# dsPIC_Click_Analog_v1_5.net
KiCad netlist of a schematic drawn in Altium Designer
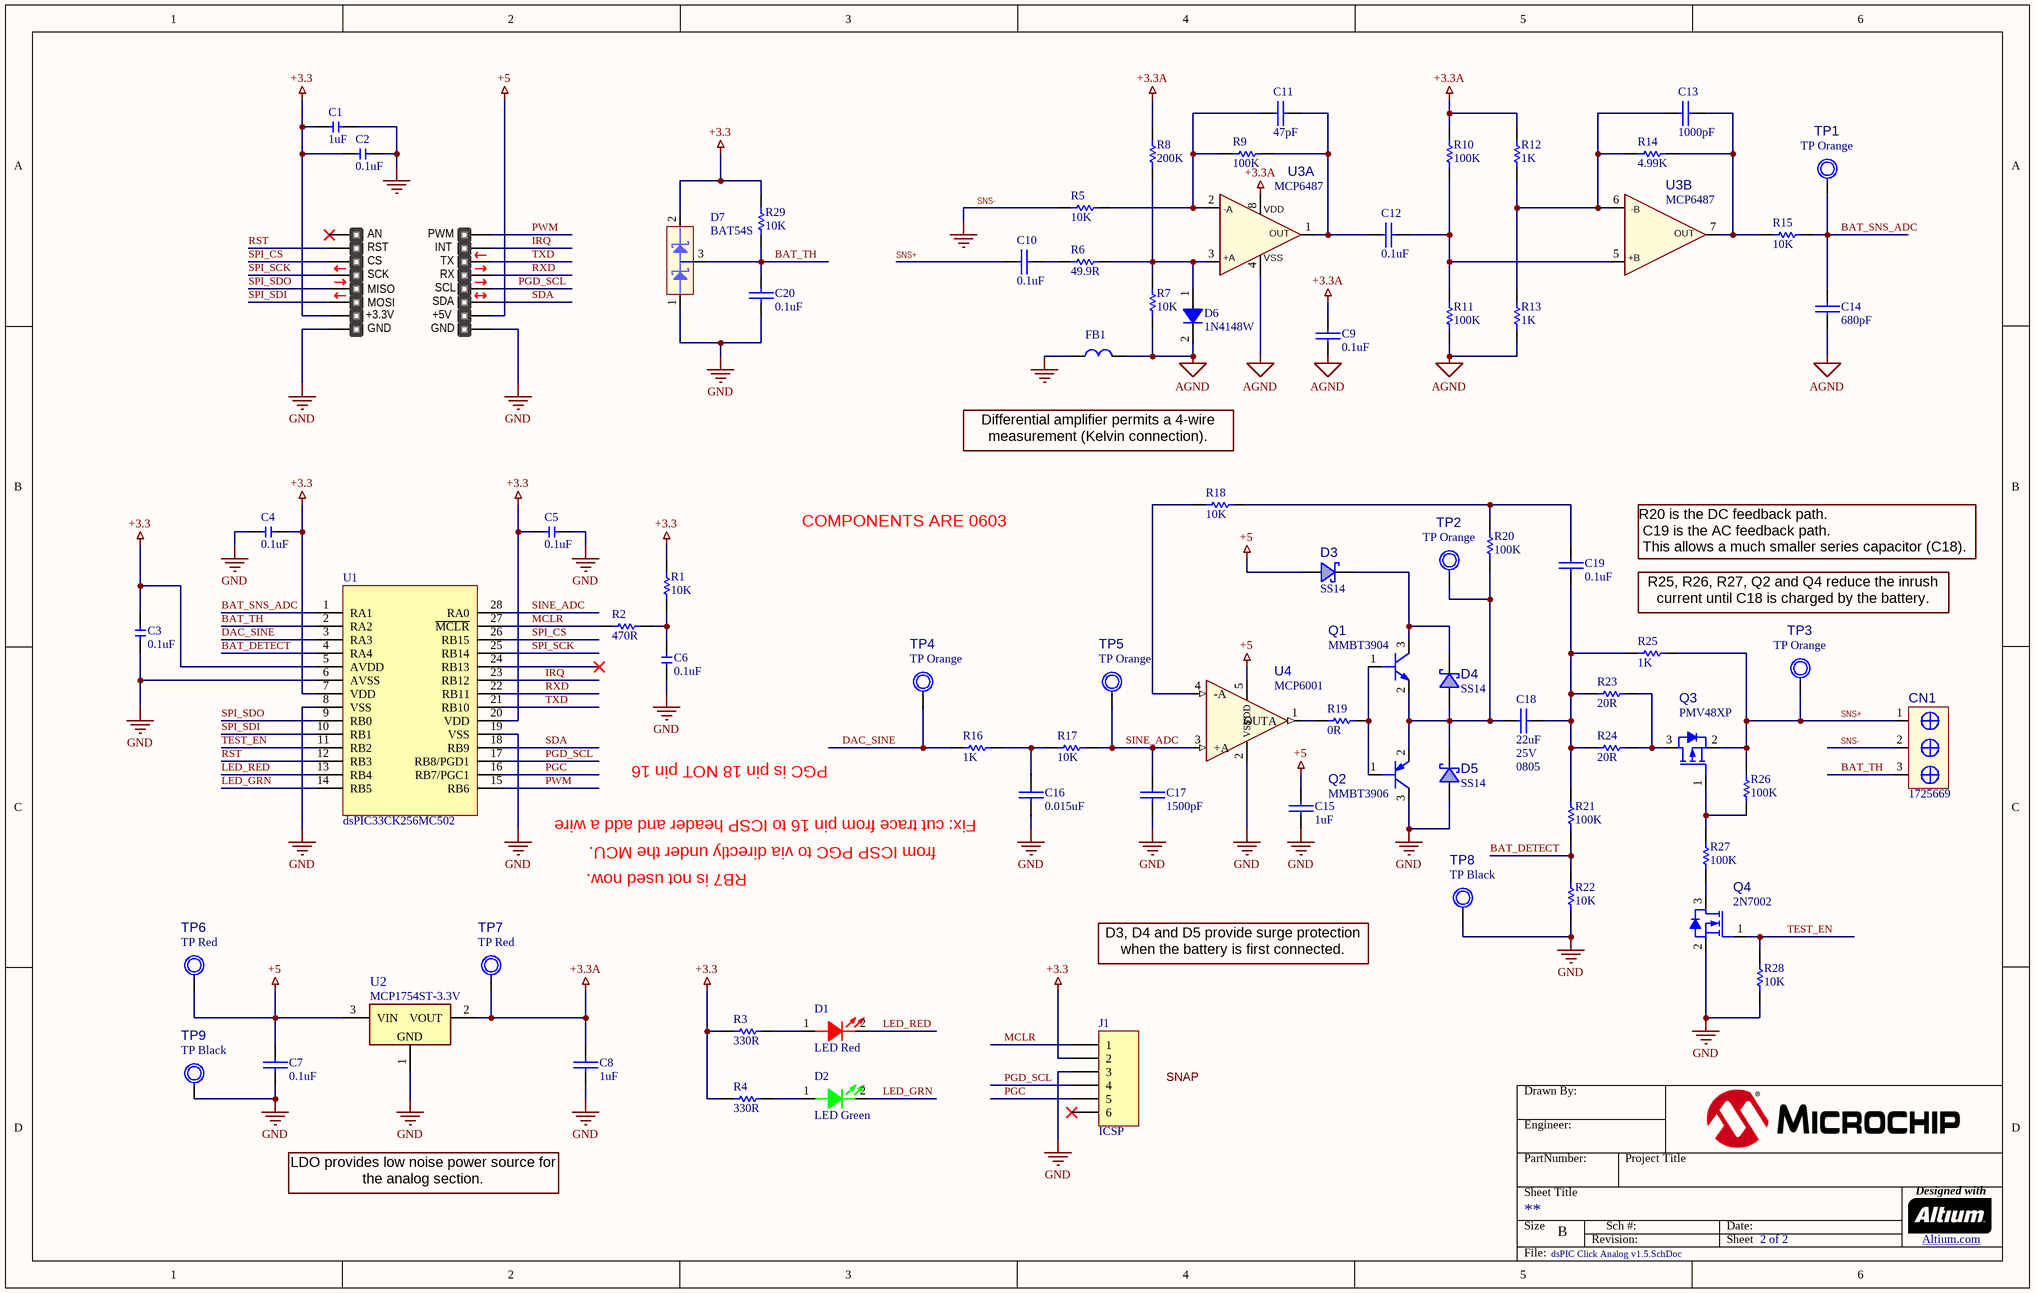
[diagram p0: dsPIC Click Analog v1.5.SchDoc]

(export (version "E")
  (design (tool "Eeschema 10.0.6"))
  (components
    (comp (ref "C1")
      (value "1uF")
      (footprint "0603C")
      (description "Capacitor")
      (libsource (lib "dsPIC Click_2") (part "Capacitor NP"))
    )
    (comp (ref "C2")
      (value "0.1uF")
      (footprint "0603C")
      (description "Capacitor")
      (libsource (lib "dsPIC Click_2") (part "Capacitor NP"))
    )
    (comp (ref "C3")
      (value "0.1uF")
      (footprint "0603C")
      (description "Capacitor")
      (libsource (lib "dsPIC Click_2") (part "Capacitor NP"))
    )
    (comp (ref "C4")
      (value "0.1uF")
      (footprint "0603C")
      (description "Capacitor")
      (libsource (lib "dsPIC Click_2") (part "Capacitor NP"))
    )
    (comp (ref "C5")
      (value "0.1uF")
      (footprint "0603C")
      (description "Capacitor")
      (libsource (lib "dsPIC Click_2") (part "Capacitor NP"))
    )
    (comp (ref "C6")
      (value "0.1uF")
      (footprint "0603C")
      (description "Capacitor")
      (libsource (lib "dsPIC Click_2") (part "Capacitor NP"))
    )
    (comp (ref "C7")
      (value "0.1uF")
      (footprint "0603C")
      (description "Capacitor")
      (libsource (lib "dsPIC Click_2") (part "CAP"))
    )
    (comp (ref "C8")
      (value "1uF")
      (footprint "0603C")
      (description "Capacitor")
      (libsource (lib "dsPIC Click_2") (part "CAP"))
    )
    (comp (ref "C9")
      (value "0.1uF")
      (footprint "0603C")
      (description "Capacitor")
      (libsource (lib "dsPIC Click_2") (part "CAP"))
    )
    (comp (ref "C10")
      (value "0.1uF")
      (footprint "0603C")
      (description "Capacitor")
      (libsource (lib "dsPIC Click_2") (part "CAP"))
    )
    (comp (ref "C11")
      (value "47pF")
      (footprint "0603C")
      (description "Capacitor")
      (libsource (lib "dsPIC Click_2") (part "CAP"))
    )
    (comp (ref "C12")
      (value "0.1uF")
      (footprint "0603C")
      (description "Capacitor")
      (libsource (lib "dsPIC Click_2") (part "CAP"))
    )
    (comp (ref "C13")
      (value "1000pF")
      (footprint "0603C")
      (description "Capacitor")
      (libsource (lib "dsPIC Click_2") (part "CAP"))
    )
    (comp (ref "C14")
      (value "680pF")
      (footprint "0603C")
      (description "Capacitor")
      (libsource (lib "dsPIC Click_2") (part "CAP"))
    )
    (comp (ref "C15")
      (value "1uF")
      (footprint "0603C")
      (description "Capacitor")
      (libsource (lib "dsPIC Click_2") (part "CAP"))
    )
    (comp (ref "C16")
      (value "0.015uF")
      (footprint "0603C")
      (description "Capacitor")
      (libsource (lib "dsPIC Click_2") (part "CAP"))
    )
    (comp (ref "C17")
      (value "1500pF")
      (footprint "0603C")
      (description "Capacitor")
      (libsource (lib "dsPIC Click_2") (part "CAP"))
    )
    (comp (ref "C18")
      (value "22uF")
      (footprint "0805C")
      (description "Capacitor")
      (fields (field (name "ALTIUM_UNNAMED_1") "25V") (field (name "ALTIUM_UNNAMED_2") "0805"))
      (libsource (lib "dsPIC Click_2") (part "CAP"))
    )
    (comp (ref "C19")
      (value "0.1uF")
      (footprint "0603C")
      (description "Capacitor")
      (libsource (lib "dsPIC Click_2") (part "CAP"))
    )
    (comp (ref "C20")
      (value "0.1uF")
      (footprint "0603C")
      (description "Capacitor")
      (libsource (lib "dsPIC Click_2") (part "CAP"))
    )
    (comp (ref "CN1")
      (value "1725669")
      (footprint "1725669")
      (description "Terminal Block, 3-Position")
      (fields (field (name "VOLTAGE") "63V") (field (name "OWNER") "Sorin Stanoaia"))
      (libsource (lib "dsPIC Click_2") (part "1725669"))
    )
    (comp (ref "D1")
      (value "LED Red")
      (footprint "LTST-C171")
      (description "Red LED")
      (fields (field (name "POWER") "50mW") (field (name "OWNER") "Stephen Humberd"))
      (libsource (lib "dsPIC Click_2") (part "LED_RED"))
    )
    (comp (ref "D2")
      (value "LED Green")
      (footprint "LTST-C171")
      (description "Green LED")
      (fields (field (name "POWER") "50mW") (field (name "OWNER") "Stephen Humberd"))
      (libsource (lib "dsPIC Click_2") (part "LED_GRN"))
    )
    (comp (ref "D3")
      (value "SS14")
      (footprint "SMA-FL")
      (description "Diode, Schottky")
      (fields (field (name "POWER") "1.1W"))
      (libsource (lib "dsPIC Click_2") (part "SS14"))
    )
    (comp (ref "D4")
      (value "SS14")
      (footprint "SMA-FL")
      (description "Diode, Schottky")
      (fields (field (name "POWER") "1.1W"))
      (libsource (lib "dsPIC Click_2") (part "SS14"))
    )
    (comp (ref "D5")
      (value "SS14")
      (footprint "SMA-FL")
      (description "Diode, Schottky")
      (fields (field (name "POWER") "1.1W"))
      (libsource (lib "dsPIC Click_2") (part "SS14"))
    )
    (comp (ref "D6")
      (value "1N4148W")
      (footprint "SOD-123")
      (description "1N4148W, SOD-123")
      (libsource (lib "dsPIC Click_2") (part "1N4148W"))
    )
    (comp (ref "D7")
      (value "BAT54S")
      (footprint "SOT-23")
      (description "Schottky Diode, Dual, Common Cathode")
      (fields (field (name "PUBLISHER") "Altium Limited"))
      (libsource (lib "dsPIC Click_2") (part "BAT54S"))
    )
    (comp (ref "FB1")
      (value "FB")
      (footprint "0603FB")
      (description "Ferrite Bead")
      (libsource (lib "dsPIC Click_2") (part "FB"))
    )
    (comp (ref "J1")
      (value "ICSP")
      (footprint "HDR1X6")
      (description "Header, 6-Pin")
      (fields (field (name "PUBLISHER") "Altium Limited"))
      (libsource (lib "dsPIC Click_2") (part "Header 6"))
    )
    (comp (ref "MIKROBUS CONNECTOR")
      (value "MIKROBUS DEVICE CONN.")
      (footprint "MIKRO_BUS_dsPIC_T")
      (description "mikroBUS Target Header")
      (libsource (lib "dsPIC Click_2") (part "MIKROBUS DEVICE CONN."))
    )
    (comp (ref "Q1")
      (value "MMBT3904")
      (footprint "SOT-23")
      (description "Transistor, NPN")
      (fields (field (name "POWER") "310mW") (field (name "VOLTAGE") "40V"))
      (libsource (lib "dsPIC Click_2") (part "MMBT3904"))
    )
    (comp (ref "Q2")
      (value "MMBT3906")
      (footprint "SOT-23")
      (description "Transistor, PNP")
      (fields (field (name "POWER") "300mW") (field (name "VOLTAGE") "-40V"))
      (libsource (lib "dsPIC Click_2") (part "MMBT3906"))
    )
    (comp (ref "Q3")
      (value "PMV48XP")
      (footprint "SOT-23")
      (description "MOSFET, P-Channel")
      (fields (field (name "POWER") "510mW") (field (name "OWNER") "Gabor Bihari"))
      (libsource (lib "dsPIC Click_2") (part "PMV48XP"))
    )
    (comp (ref "Q4")
      (value "2N7002")
      (footprint "SOT-23")
      (description "MOSFET")
      (fields (field (name "POWER") "370mW") (field (name "OWNER") "Adrian M (M91404)"))
      (libsource (lib "dsPIC Click_2") (part "2N7002"))
    )
    (comp (ref "R1")
      (value "10K")
      (footprint "0603R")
      (description "Resistor")
      (fields (field (name "PUBLISHER") "Altium Limited"))
      (libsource (lib "dsPIC Click_2") (part "Res1"))
    )
    (comp (ref "R2")
      (value "470R")
      (footprint "0603R")
      (description "Resistor")
      (fields (field (name "PUBLISHER") "Altium Limited"))
      (libsource (lib "dsPIC Click_2") (part "Res1"))
    )
    (comp (ref "R3")
      (value "330R")
      (footprint "0603R")
      (description "Resistor")
      (fields (field (name "PUBLISHER") "Altium Limited"))
      (libsource (lib "dsPIC Click_2") (part "Res1"))
    )
    (comp (ref "R4")
      (value "330R")
      (footprint "0603R")
      (description "Resistor")
      (fields (field (name "PUBLISHER") "Altium Limited"))
      (libsource (lib "dsPIC Click_2") (part "Res1"))
    )
    (comp (ref "R5")
      (value "10K")
      (footprint "0603R")
      (description "Resistor")
      (fields (field (name "PUBLISHER") "Altium Limited"))
      (libsource (lib "dsPIC Click_2") (part "Res1"))
    )
    (comp (ref "R6")
      (value "49.9R")
      (footprint "0603R")
      (description "Resistor")
      (fields (field (name "PUBLISHER") "Altium Limited"))
      (libsource (lib "dsPIC Click_2") (part "Res1"))
    )
    (comp (ref "R7")
      (value "10K")
      (footprint "0603R")
      (description "Resistor")
      (fields (field (name "PUBLISHER") "Altium Limited"))
      (libsource (lib "dsPIC Click_2") (part "Res1"))
    )
    (comp (ref "R8")
      (value "200K")
      (footprint "0603R")
      (description "Resistor")
      (fields (field (name "PUBLISHER") "Altium Limited"))
      (libsource (lib "dsPIC Click_2") (part "Res1"))
    )
    (comp (ref "R9")
      (value "100K")
      (footprint "0603R")
      (description "Resistor")
      (fields (field (name "PUBLISHER") "Altium Limited"))
      (libsource (lib "dsPIC Click_2") (part "Res1"))
    )
    (comp (ref "R10")
      (value "100K")
      (footprint "0603R")
      (description "Resistor")
      (fields (field (name "PUBLISHER") "Altium Limited"))
      (libsource (lib "dsPIC Click_2") (part "Res1"))
    )
    (comp (ref "R11")
      (value "100K")
      (footprint "0603R")
      (description "Resistor")
      (fields (field (name "PUBLISHER") "Altium Limited"))
      (libsource (lib "dsPIC Click_2") (part "Res1"))
    )
    (comp (ref "R12")
      (value "1K")
      (footprint "0603R")
      (description "Resistor")
      (fields (field (name "PUBLISHER") "Altium Limited"))
      (libsource (lib "dsPIC Click_2") (part "Res1"))
    )
    (comp (ref "R13")
      (value "1K")
      (footprint "0603R")
      (description "Resistor")
      (fields (field (name "PUBLISHER") "Altium Limited"))
      (libsource (lib "dsPIC Click_2") (part "Res1"))
    )
    (comp (ref "R14")
      (value "4.99K")
      (footprint "0603R")
      (description "Resistor")
      (fields (field (name "PUBLISHER") "Altium Limited"))
      (libsource (lib "dsPIC Click_2") (part "Res1"))
    )
    (comp (ref "R15")
      (value "10K")
      (footprint "0603R")
      (description "Resistor")
      (fields (field (name "PUBLISHER") "Altium Limited"))
      (libsource (lib "dsPIC Click_2") (part "Res1"))
    )
    (comp (ref "R16")
      (value "1K")
      (footprint "0603R")
      (description "Resistor")
      (fields (field (name "PUBLISHER") "Altium Limited"))
      (libsource (lib "dsPIC Click_2") (part "Res1"))
    )
    (comp (ref "R17")
      (value "10K")
      (footprint "0603R")
      (description "Resistor")
      (fields (field (name "PUBLISHER") "Altium Limited"))
      (libsource (lib "dsPIC Click_2") (part "Res1"))
    )
    (comp (ref "R18")
      (value "10K")
      (footprint "0603R")
      (description "Resistor")
      (fields (field (name "PUBLISHER") "Altium Limited"))
      (libsource (lib "dsPIC Click_2") (part "Res1"))
    )
    (comp (ref "R19")
      (value "0R")
      (footprint "0603R")
      (description "Resistor")
      (fields (field (name "PUBLISHER") "Altium Limited"))
      (libsource (lib "dsPIC Click_2") (part "Res1"))
    )
    (comp (ref "R20")
      (value "100K")
      (footprint "0603R")
      (description "Resistor")
      (fields (field (name "PUBLISHER") "Altium Limited"))
      (libsource (lib "dsPIC Click_2") (part "Res1"))
    )
    (comp (ref "R21")
      (value "100K")
      (footprint "0603R")
      (description "Resistor")
      (fields (field (name "PUBLISHER") "Altium Limited"))
      (libsource (lib "dsPIC Click_2") (part "Res1"))
    )
    (comp (ref "R22")
      (value "10K")
      (footprint "0603R")
      (description "Resistor")
      (fields (field (name "PUBLISHER") "Altium Limited"))
      (libsource (lib "dsPIC Click_2") (part "Res1"))
    )
    (comp (ref "R23")
      (value "20R")
      (footprint "0603R")
      (description "Resistor")
      (fields (field (name "PUBLISHER") "Altium Limited"))
      (libsource (lib "dsPIC Click_2") (part "Res1"))
    )
    (comp (ref "R24")
      (value "20R")
      (footprint "0603R")
      (description "Resistor")
      (fields (field (name "PUBLISHER") "Altium Limited"))
      (libsource (lib "dsPIC Click_2") (part "Res1"))
    )
    (comp (ref "R25")
      (value "1K")
      (footprint "0603R")
      (description "Resistor")
      (fields (field (name "PUBLISHER") "Altium Limited"))
      (libsource (lib "dsPIC Click_2") (part "Res1"))
    )
    (comp (ref "R26")
      (value "100K")
      (footprint "0603R")
      (description "Resistor")
      (fields (field (name "PUBLISHER") "Altium Limited"))
      (libsource (lib "dsPIC Click_2") (part "Res1"))
    )
    (comp (ref "R27")
      (value "100K")
      (footprint "0603R")
      (description "Resistor")
      (fields (field (name "PUBLISHER") "Altium Limited"))
      (libsource (lib "dsPIC Click_2") (part "Res1"))
    )
    (comp (ref "R28")
      (value "10K")
      (footprint "0603R")
      (description "Resistor")
      (fields (field (name "PUBLISHER") "Altium Limited"))
      (libsource (lib "dsPIC Click_2") (part "Res1"))
    )
    (comp (ref "R29")
      (value "10K")
      (footprint "0603R")
      (description "Resistor")
      (fields (field (name "PUBLISHER") "Altium Limited"))
      (libsource (lib "dsPIC Click_2") (part "Res1"))
    )
    (comp (ref "TP1")
      (value "Test Point Orange")
      (footprint "TP_KEYSTONE_5003")
      (description "Test Point, 5003")
      (fields (field (name "ALTIUM_UNNAMED_1") "TP Orange"))
      (libsource (lib "dsPIC Click_2") (part "Test Point Orange"))
    )
    (comp (ref "TP2")
      (value "Test Point Orange")
      (footprint "TP_KEYSTONE_5003")
      (description "Test Point, 5003")
      (fields (field (name "ALTIUM_UNNAMED_1") "TP Orange"))
      (libsource (lib "dsPIC Click_2") (part "Test Point Orange"))
    )
    (comp (ref "TP3")
      (value "Test Point Orange")
      (footprint "TP_KEYSTONE_5003")
      (description "Test Point, 5003")
      (fields (field (name "ALTIUM_UNNAMED_1") "TP Orange"))
      (libsource (lib "dsPIC Click_2") (part "Test Point Orange"))
    )
    (comp (ref "TP4")
      (value "Test Point Orange")
      (footprint "TP_KEYSTONE_5003")
      (description "Test Point, 5003")
      (fields (field (name "ALTIUM_UNNAMED_1") "TP Orange"))
      (libsource (lib "dsPIC Click_2") (part "Test Point Orange"))
    )
    (comp (ref "TP5")
      (value "Test Point Orange")
      (footprint "TP_KEYSTONE_5003")
      (description "Test Point, 5003")
      (fields (field (name "ALTIUM_UNNAMED_1") "TP Orange"))
      (libsource (lib "dsPIC Click_2") (part "Test Point Orange"))
    )
    (comp (ref "TP6")
      (value "Test Point Red")
      (footprint "TP_KEYSTONE_5000")
      (description "Test Point, 5000")
      (fields (field (name "ALTIUM_UNNAMED_1") "TP Red"))
      (libsource (lib "dsPIC Click_2") (part "Test Point Red"))
    )
    (comp (ref "TP7")
      (value "Test Point Red")
      (footprint "TP_KEYSTONE_5000")
      (description "Test Point, 5000")
      (fields (field (name "ALTIUM_UNNAMED_1") "TP Red"))
      (libsource (lib "dsPIC Click_2") (part "Test Point Red"))
    )
    (comp (ref "TP8")
      (value "Test Point Black")
      (footprint "TP_KEYSTONE_5001")
      (description "Test Point, 5001")
      (fields (field (name "ALTIUM_UNNAMED_1") "TP Black"))
      (libsource (lib "dsPIC Click_2") (part "Test Point Black"))
    )
    (comp (ref "TP9")
      (value "Test Point Black")
      (footprint "TP_KEYSTONE_5001")
      (description "Test Point, 5001")
      (fields (field (name "ALTIUM_UNNAMED_1") "TP Black"))
      (libsource (lib "dsPIC Click_2") (part "Test Point Black"))
    )
    (comp (ref "U1")
      (value "dsPIC33CK256MC502")
      (footprint "SSOP-28")
      (description "16-bit MCU")
      (libsource (lib "dsPIC Click_2") (part "dsPIC33CK256MC502"))
    )
    (comp (ref "U2")
      (value "MCP1754ST-3.3V")
      (footprint "SOT-23")
      (description "LDO")
      (fields (field (name "OWNER") "Iulian Margarit"))
      (libsource (lib "dsPIC Click_2") (part "MCP1754S"))
    )
    (comp (ref "U3")
      (value "MCP6487")
      (footprint "SOIC-8")
      (description "OPAMP, Dual")
      (libsource (lib "dsPIC Click_2") (part "MCP6487"))
    )
    (comp (ref "U4")
      (value "MCP6001")
      (footprint "TSOP-5")
      (description "OPAMP, Single")
      (fields (field (name "OWNER") "Ryan Hermens"))
      (libsource (lib "dsPIC Click_2") (part "MCP6001"))
    )
  )
  (nets
    (net (code "1") (name "+3.3") (class "Default")
      (node (ref "C1") (pin "1") (pinfunction "1_1") (pintype "passive"))
      (node (ref "C2") (pin "1") (pinfunction "1_1") (pintype "passive"))
      (node (ref "C3") (pin "2") (pinfunction "2_2") (pintype "passive"))
      (node (ref "C4") (pin "1") (pinfunction "1_1") (pintype "passive"))
      (node (ref "C5") (pin "2") (pinfunction "2_2") (pintype "passive"))
      (node (ref "D7") (pin "2") (pinfunction "K_2") (pintype "passive"))
      (node (ref "J1") (pin "2") (pinfunction "2_2") (pintype "passive"))
      (node (ref "MIKROBUS CONNECTOR") (pin "7") (pinfunction "3.3V_7") (pintype "passive"))
      (node (ref "R1") (pin "2") (pinfunction "2_2") (pintype "passive"))
      (node (ref "R29") (pin "2") (pinfunction "2_2") (pintype "passive"))
      (node (ref "R3") (pin "2") (pinfunction "2_2") (pintype "passive"))
      (node (ref "R4") (pin "2") (pinfunction "2_2") (pintype "passive"))
      (node (ref "U1") (pin "20") (pinfunction "VDD_20") (pintype "passive"))
      (node (ref "U1") (pin "5") (pinfunction "AVDD_5") (pintype "passive"))
      (node (ref "U1") (pin "7") (pinfunction "VDD_7") (pintype "passive"))
    )
    (net (code "2") (name "+3.3A") (class "Default")
      (node (ref "C8") (pin "1") (pinfunction "1_1") (pintype "passive"))
      (node (ref "C9") (pin "1") (pinfunction "1_1") (pintype "passive"))
      (node (ref "R10") (pin "2") (pinfunction "2_2") (pintype "passive"))
      (node (ref "R12") (pin "2") (pinfunction "2_2") (pintype "passive"))
      (node (ref "R8") (pin "2") (pinfunction "2_2") (pintype "passive"))
      (node (ref "TP7") (pin "1") (pinfunction "1_1") (pintype "passive"))
      (node (ref "U2") (pin "2") (pinfunction "VOUT_2") (pintype "power_in"))
      (node (ref "U3") (pin "8") (pinfunction "VDD_8") (pintype "power_in"))
    )
    (net (code "3") (name "+5") (class "Default")
      (node (ref "C15") (pin "1") (pinfunction "1_1") (pintype "passive"))
      (node (ref "C7") (pin "1") (pinfunction "1_1") (pintype "passive"))
      (node (ref "D3") (pin "1") (pinfunction "A_1") (pintype "passive"))
      (node (ref "MIKROBUS CONNECTOR") (pin "10") (pinfunction "5V_10") (pintype "passive"))
      (node (ref "TP6") (pin "1") (pinfunction "1_1") (pintype "passive"))
      (node (ref "U2") (pin "3") (pinfunction "VIN_3") (pintype "power_in"))
      (node (ref "U4") (pin "5") (pinfunction "VDD_5") (pintype "power_in"))
    )
    (net (code "4") (name "/BAT_DETECT") (class "Default")
      (node (ref "R21") (pin "1") (pinfunction "1_1") (pintype "passive"))
      (node (ref "R22") (pin "2") (pinfunction "2_2") (pintype "passive"))
      (node (ref "U1") (pin "4") (pinfunction "RA4_4") (pintype "passive"))
    )
    (net (code "5") (name "/BAT_SNS_ADC") (class "Default")
      (node (ref "C14") (pin "2") (pinfunction "2_2") (pintype "passive"))
      (node (ref "R15") (pin "1") (pinfunction "1_1") (pintype "passive"))
      (node (ref "TP1") (pin "1") (pinfunction "1_1") (pintype "passive"))
      (node (ref "U1") (pin "1") (pinfunction "RA1_1") (pintype "passive"))
    )
    (net (code "6") (name "/BAT_TH") (class "Default")
      (node (ref "C20") (pin "1") (pinfunction "1_1") (pintype "passive"))
      (node (ref "CN1") (pin "3") (pinfunction "3_3") (pintype "passive"))
      (node (ref "D7") (pin "3") (pinfunction "AK_3") (pintype "passive"))
      (node (ref "R29") (pin "1") (pinfunction "1_1") (pintype "passive"))
      (node (ref "U1") (pin "2") (pinfunction "RA2_2") (pintype "passive"))
    )
    (net (code "7") (name "/DAC_SINE") (class "Default")
      (node (ref "R16") (pin "1") (pinfunction "1_1") (pintype "passive"))
      (node (ref "TP4") (pin "1") (pinfunction "1_1") (pintype "passive"))
      (node (ref "U1") (pin "3") (pinfunction "RA3_3") (pintype "passive"))
    )
    (net (code "8") (name "/IRQ") (class "Default")
      (node (ref "MIKROBUS CONNECTOR") (pin "15") (pinfunction "INT_15") (pintype "passive"))
      (node (ref "U1") (pin "23") (pinfunction "RB12_23") (pintype "passive"))
    )
    (net (code "9") (name "/LED_GRN") (class "Default")
      (node (ref "D2") (pin "2") (pinfunction "K_2") (pintype "passive"))
      (node (ref "U1") (pin "14") (pinfunction "RB5_14") (pintype "passive"))
    )
    (net (code "10") (name "/LED_RED") (class "Default")
      (node (ref "D1") (pin "2") (pinfunction "K_2") (pintype "passive"))
      (node (ref "U1") (pin "13") (pinfunction "RB4_13") (pintype "passive"))
    )
    (net (code "11") (name "/MCLR") (class "Default")
      (node (ref "J1") (pin "1") (pinfunction "1_1") (pintype "passive"))
      (node (ref "R2") (pin "2") (pinfunction "2_2") (pintype "passive"))
      (node (ref "U1") (pin "27") (pinfunction "~{MCLR}_27") (pintype "passive"))
    )
    (net (code "12") (name "/PGC") (class "Default")
      (node (ref "J1") (pin "5") (pinfunction "5_5") (pintype "passive"))
      (node (ref "U1") (pin "16") (pinfunction "RB7/PGC1_16") (pintype "passive"))
    )
    (net (code "13") (name "/PGD_SCL") (class "Default")
      (node (ref "J1") (pin "4") (pinfunction "4_4") (pintype "passive"))
      (node (ref "MIKROBUS CONNECTOR") (pin "12") (pinfunction "SCL_12") (pintype "passive"))
      (node (ref "U1") (pin "17") (pinfunction "RB8/PGD1_17") (pintype "passive"))
    )
    (net (code "14") (name "/PWM") (class "Default")
      (node (ref "MIKROBUS CONNECTOR") (pin "16") (pinfunction "PWM_16") (pintype "passive"))
      (node (ref "U1") (pin "15") (pinfunction "RB6_15") (pintype "passive"))
    )
    (net (code "15") (name "/RST") (class "Default")
      (node (ref "MIKROBUS CONNECTOR") (pin "2") (pinfunction "RST_2") (pintype "passive"))
      (node (ref "U1") (pin "12") (pinfunction "RB3_12") (pintype "passive"))
    )
    (net (code "16") (name "/RXD") (class "Default")
      (node (ref "MIKROBUS CONNECTOR") (pin "13") (pinfunction "TX_13") (pintype "passive"))
      (node (ref "U1") (pin "22") (pinfunction "RB11_22") (pintype "passive"))
    )
    (net (code "17") (name "/SDA") (class "Default")
      (node (ref "MIKROBUS CONNECTOR") (pin "11") (pinfunction "SDA_11") (pintype "passive"))
      (node (ref "U1") (pin "18") (pinfunction "RB9_18") (pintype "passive"))
    )
    (net (code "18") (name "/SINE_ADC") (class "Default")
      (node (ref "C17") (pin "1") (pinfunction "1_1") (pintype "passive"))
      (node (ref "R17") (pin "2") (pinfunction "2_2") (pintype "passive"))
      (node (ref "TP5") (pin "1") (pinfunction "1_1") (pintype "passive"))
      (node (ref "U1") (pin "28") (pinfunction "RA0_28") (pintype "passive"))
      (node (ref "U4") (pin "3") (pinfunction "+A_3") (pintype "input"))
    )
    (net (code "19") (name "/SNS+") (class "Default")
      (node (ref "C10") (pin "1") (pinfunction "1_1") (pintype "passive"))
      (node (ref "CN1") (pin "1") (pinfunction "1_1") (pintype "passive"))
      (node (ref "Q3") (pin "2") (pinfunction "S_2") (pintype "passive"))
      (node (ref "R25") (pin "1") (pinfunction "1_1") (pintype "passive"))
      (node (ref "R26") (pin "1") (pinfunction "1_1") (pintype "passive"))
      (node (ref "TP3") (pin "1") (pinfunction "1_1") (pintype "passive"))
    )
    (net (code "20") (name "/SPI_CS") (class "Default")
      (node (ref "MIKROBUS CONNECTOR") (pin "3") (pinfunction "CS_3") (pintype "passive"))
      (node (ref "U1") (pin "26") (pinfunction "RB15_26") (pintype "passive"))
    )
    (net (code "21") (name "/SPI_SCK") (class "Default")
      (node (ref "MIKROBUS CONNECTOR") (pin "4") (pinfunction "SCK_4") (pintype "passive"))
      (node (ref "U1") (pin "25") (pinfunction "RB14_25") (pintype "passive"))
    )
    (net (code "22") (name "/SPI_SDI") (class "Default")
      (node (ref "MIKROBUS CONNECTOR") (pin "6") (pinfunction "MOSI_6") (pintype "passive"))
      (node (ref "U1") (pin "10") (pinfunction "RB1_10") (pintype "passive"))
    )
    (net (code "23") (name "/SPI_SDO") (class "Default")
      (node (ref "MIKROBUS CONNECTOR") (pin "5") (pinfunction "MISO_5") (pintype "passive"))
      (node (ref "U1") (pin "9") (pinfunction "RB0_9") (pintype "passive"))
    )
    (net (code "24") (name "/TEST_EN") (class "Default")
      (node (ref "Q4") (pin "1") (pinfunction "G_1") (pintype "passive"))
      (node (ref "R28") (pin "1") (pinfunction "1_1") (pintype "passive"))
      (node (ref "U1") (pin "11") (pinfunction "RB2_11") (pintype "passive"))
    )
    (net (code "25") (name "/TXD") (class "Default")
      (node (ref "MIKROBUS CONNECTOR") (pin "14") (pinfunction "RX_14") (pintype "passive"))
      (node (ref "U1") (pin "21") (pinfunction "RB10_21") (pintype "passive"))
    )
    (net (code "26") (name "AGND") (class "Default")
      (node (ref "C14") (pin "1") (pinfunction "1_1") (pintype "passive"))
      (node (ref "C9") (pin "2") (pinfunction "2_2") (pintype "passive"))
      (node (ref "D6") (pin "2") (pinfunction "K_2") (pintype "passive"))
      (node (ref "FB1") (pin "2") (pinfunction "2_2") (pintype "passive"))
      (node (ref "R11") (pin "1") (pinfunction "1_1") (pintype "passive"))
      (node (ref "R13") (pin "1") (pinfunction "1_1") (pintype "passive"))
      (node (ref "R7") (pin "1") (pinfunction "1_1") (pintype "passive"))
      (node (ref "U3") (pin "4") (pinfunction "VSS_4") (pintype "power_in"))
    )
    (net (code "27") (name "GND") (class "Default")
      (node (ref "C1") (pin "2") (pinfunction "2_2") (pintype "passive"))
      (node (ref "C15") (pin "2") (pinfunction "2_2") (pintype "passive"))
      (node (ref "C16") (pin "2") (pinfunction "2_2") (pintype "passive"))
      (node (ref "C17") (pin "2") (pinfunction "2_2") (pintype "passive"))
      (node (ref "C2") (pin "2") (pinfunction "2_2") (pintype "passive"))
      (node (ref "C20") (pin "2") (pinfunction "2_2") (pintype "passive"))
      (node (ref "C3") (pin "1") (pinfunction "1_1") (pintype "passive"))
      (node (ref "C4") (pin "2") (pinfunction "2_2") (pintype "passive"))
      (node (ref "C5") (pin "1") (pinfunction "1_1") (pintype "passive"))
      (node (ref "C6") (pin "2") (pinfunction "2_2") (pintype "passive"))
      (node (ref "C7") (pin "2") (pinfunction "2_2") (pintype "passive"))
      (node (ref "C8") (pin "2") (pinfunction "2_2") (pintype "passive"))
      (node (ref "CN1") (pin "2") (pinfunction "2_2") (pintype "passive"))
      (node (ref "D5") (pin "1") (pinfunction "A_1") (pintype "passive"))
      (node (ref "D7") (pin "1") (pinfunction "A1_1") (pintype "passive"))
      (node (ref "FB1") (pin "1") (pinfunction "1_1") (pintype "passive"))
      (node (ref "J1") (pin "3") (pinfunction "3_3") (pintype "passive"))
      (node (ref "MIKROBUS CONNECTOR") (pin "8") (pinfunction "GND_8") (pintype "passive"))
      (node (ref "MIKROBUS CONNECTOR") (pin "9") (pinfunction "GND_9") (pintype "passive"))
      (node (ref "Q2") (pin "3") (pinfunction "C_3") (pintype "passive"))
      (node (ref "Q4") (pin "2") (pinfunction "S_2") (pintype "passive"))
      (node (ref "R22") (pin "1") (pinfunction "1_1") (pintype "passive"))
      (node (ref "R28") (pin "2") (pinfunction "2_2") (pintype "passive"))
      (node (ref "R5") (pin "1") (pinfunction "1_1") (pintype "passive"))
      (node (ref "TP8") (pin "1") (pinfunction "1_1") (pintype "passive"))
      (node (ref "TP9") (pin "1") (pinfunction "1_1") (pintype "passive"))
      (node (ref "U1") (pin "19") (pinfunction "VSS_19") (pintype "passive"))
      (node (ref "U1") (pin "6") (pinfunction "AVSS_6") (pintype "passive"))
      (node (ref "U1") (pin "8") (pinfunction "VSS_8") (pintype "passive"))
      (node (ref "U2") (pin "1") (pinfunction "GND_1") (pintype "power_in"))
      (node (ref "U4") (pin "2") (pinfunction "VSS_2") (pintype "power_in"))
    )
    (net (code "28") (name "Net-(C6-Pad1)") (class "Default")
      (node (ref "C6") (pin "1") (pinfunction "1_1") (pintype "passive"))
      (node (ref "R1") (pin "1") (pinfunction "1_1") (pintype "passive"))
      (node (ref "R2") (pin "1") (pinfunction "1_1") (pintype "passive"))
    )
    (net (code "29") (name "Net-(C10-Pad2)") (class "Default")
      (node (ref "C10") (pin "2") (pinfunction "2_2") (pintype "passive"))
      (node (ref "R6") (pin "1") (pinfunction "1_1") (pintype "passive"))
    )
    (net (code "30") (name "Net-(C16-Pad1)") (class "Default")
      (node (ref "C16") (pin "1") (pinfunction "1_1") (pintype "passive"))
      (node (ref "R16") (pin "2") (pinfunction "2_2") (pintype "passive"))
      (node (ref "R17") (pin "1") (pinfunction "1_1") (pintype "passive"))
    )
    (net (code "31") (name "Net-(C18-Pad2)") (class "Default")
      (node (ref "C18") (pin "2") (pinfunction "2_2") (pintype "passive"))
      (node (ref "C19") (pin "2") (pinfunction "2_2") (pintype "passive"))
      (node (ref "R21") (pin "2") (pinfunction "2_2") (pintype "passive"))
      (node (ref "R23") (pin "2") (pinfunction "2_2") (pintype "passive"))
      (node (ref "R24") (pin "2") (pinfunction "2_2") (pintype "passive"))
      (node (ref "R25") (pin "2") (pinfunction "2_2") (pintype "passive"))
    )
    (net (code "32") (name "Net-(C19-Pad1)") (class "Default")
      (node (ref "C19") (pin "1") (pinfunction "1_1") (pintype "passive"))
      (node (ref "R18") (pin "2") (pinfunction "2_2") (pintype "passive"))
      (node (ref "R20") (pin "2") (pinfunction "2_2") (pintype "passive"))
    )
    (net (code "33") (name "Net-(D1-A)") (class "Default")
      (node (ref "D1") (pin "1") (pinfunction "A_1") (pintype "passive"))
      (node (ref "R3") (pin "1") (pinfunction "1_1") (pintype "passive"))
    )
    (net (code "34") (name "Net-(D2-A)") (class "Default")
      (node (ref "D2") (pin "1") (pinfunction "A_1") (pintype "passive"))
      (node (ref "R4") (pin "1") (pinfunction "1_1") (pintype "passive"))
    )
    (net (code "35") (name "Net-(D3-K)") (class "Default")
      (node (ref "D3") (pin "2") (pinfunction "K_2") (pintype "passive"))
      (node (ref "D4") (pin "2") (pinfunction "K_2") (pintype "passive"))
      (node (ref "Q1") (pin "3") (pinfunction "C_3") (pintype "passive"))
    )
    (net (code "36") (name "Net-(D4-A)") (class "Default")
      (node (ref "C18") (pin "1") (pinfunction "1_1") (pintype "passive"))
      (node (ref "D4") (pin "1") (pinfunction "A_1") (pintype "passive"))
      (node (ref "D5") (pin "2") (pinfunction "K_2") (pintype "passive"))
      (node (ref "Q1") (pin "2") (pinfunction "E_2") (pintype "passive"))
      (node (ref "Q2") (pin "2") (pinfunction "E_2") (pintype "passive"))
      (node (ref "R20") (pin "1") (pinfunction "1_1") (pintype "passive"))
      (node (ref "TP2") (pin "1") (pinfunction "1_1") (pintype "passive"))
    )
    (net (code "37") (name "Net-(D6-A)") (class "Default")
      (node (ref "D6") (pin "1") (pinfunction "A_1") (pintype "passive"))
      (node (ref "R6") (pin "2") (pinfunction "2_2") (pintype "passive"))
      (node (ref "R7") (pin "2") (pinfunction "2_2") (pintype "passive"))
      (node (ref "R8") (pin "1") (pinfunction "1_1") (pintype "passive"))
      (node (ref "U3") (pin "3") (pinfunction "+A_3") (pintype "passive"))
    )
    (net (code "38") (name "Net-(Q1-B)") (class "Default")
      (node (ref "Q1") (pin "1") (pinfunction "B_1") (pintype "passive"))
      (node (ref "Q2") (pin "1") (pinfunction "B_1") (pintype "passive"))
      (node (ref "R19") (pin "2") (pinfunction "2_2") (pintype "passive"))
    )
    (net (code "39") (name "Net-(Q3-D)") (class "Default")
      (node (ref "Q3") (pin "3") (pinfunction "D_3") (pintype "passive"))
      (node (ref "R23") (pin "1") (pinfunction "1_1") (pintype "passive"))
      (node (ref "R24") (pin "1") (pinfunction "1_1") (pintype "passive"))
    )
    (net (code "40") (name "Net-(Q3-G)") (class "Default")
      (node (ref "Q3") (pin "1") (pinfunction "G_1") (pintype "passive"))
      (node (ref "R26") (pin "2") (pinfunction "2_2") (pintype "passive"))
      (node (ref "R27") (pin "1") (pinfunction "1_1") (pintype "passive"))
    )
    (net (code "41") (name "Net-(Q4-D)") (class "Default")
      (node (ref "Q4") (pin "3") (pinfunction "D_3") (pintype "passive"))
      (node (ref "R27") (pin "2") (pinfunction "2_2") (pintype "passive"))
    )
    (net (code "42") (name "Net-(U3A--A)") (class "Default")
      (node (ref "C11") (pin "1") (pinfunction "1_1") (pintype "passive"))
      (node (ref "R5") (pin "2") (pinfunction "2_2") (pintype "passive"))
      (node (ref "R9") (pin "2") (pinfunction "2_2") (pintype "passive"))
      (node (ref "U3") (pin "2") (pinfunction "-A_2") (pintype "passive"))
    )
    (net (code "43") (name "Net-(U3A-OUTA)") (class "Default")
      (node (ref "C11") (pin "2") (pinfunction "2_2") (pintype "passive"))
      (node (ref "C12") (pin "1") (pinfunction "1_1") (pintype "passive"))
      (node (ref "R9") (pin "1") (pinfunction "1_1") (pintype "passive"))
      (node (ref "U3") (pin "1") (pinfunction "OUTA_1") (pintype "passive"))
    )
    (net (code "44") (name "Net-(U3B-+B)") (class "Default")
      (node (ref "C12") (pin "2") (pinfunction "2_2") (pintype "passive"))
      (node (ref "R10") (pin "1") (pinfunction "1_1") (pintype "passive"))
      (node (ref "R11") (pin "2") (pinfunction "2_2") (pintype "passive"))
      (node (ref "U3") (pin "5") (pinfunction "+B_5") (pintype "passive"))
    )
    (net (code "45") (name "Net-(U3B--B)") (class "Default")
      (node (ref "C13") (pin "1") (pinfunction "1_1") (pintype "passive"))
      (node (ref "R12") (pin "1") (pinfunction "1_1") (pintype "passive"))
      (node (ref "R13") (pin "2") (pinfunction "2_2") (pintype "passive"))
      (node (ref "R14") (pin "2") (pinfunction "2_2") (pintype "passive"))
      (node (ref "U3") (pin "6") (pinfunction "-B_6") (pintype "passive"))
    )
    (net (code "46") (name "Net-(U3B-OUTB)") (class "Default")
      (node (ref "C13") (pin "2") (pinfunction "2_2") (pintype "passive"))
      (node (ref "R14") (pin "1") (pinfunction "1_1") (pintype "passive"))
      (node (ref "R15") (pin "2") (pinfunction "2_2") (pintype "passive"))
      (node (ref "U3") (pin "7") (pinfunction "OUTB_7") (pintype "passive"))
    )
    (net (code "47") (name "Net-(U4--A)") (class "Default")
      (node (ref "R18") (pin "1") (pinfunction "1_1") (pintype "passive"))
      (node (ref "U4") (pin "4") (pinfunction "-A_4") (pintype "input"))
    )
    (net (code "48") (name "Net-(U4-OUTA)") (class "Default")
      (node (ref "R19") (pin "1") (pinfunction "1_1") (pintype "passive"))
      (node (ref "U4") (pin "1") (pinfunction "OUTA_1") (pintype "output"))
    )
    (net (code "49") (name "unconnected-(J1-Pad6)") (class "Default")
      (node (ref "J1") (pin "6") (pinfunction "6_6") (pintype "passive+no_connect"))
    )
    (net (code "50") (name "unconnected-(MIKROBUS CONNECTOR-AN-Pad1)") (class "Default")
      (node (ref "MIKROBUS CONNECTOR") (pin "1") (pinfunction "AN_1") (pintype "passive+no_connect"))
    )
    (net (code "51") (name "unconnected-(U1-RB13-Pad24)") (class "Default")
      (node (ref "U1") (pin "24") (pinfunction "RB13_24") (pintype "passive+no_connect"))
    )
  )
)
